# CSKB.net
KiCad netlist of a schematic drawn in EAGLE
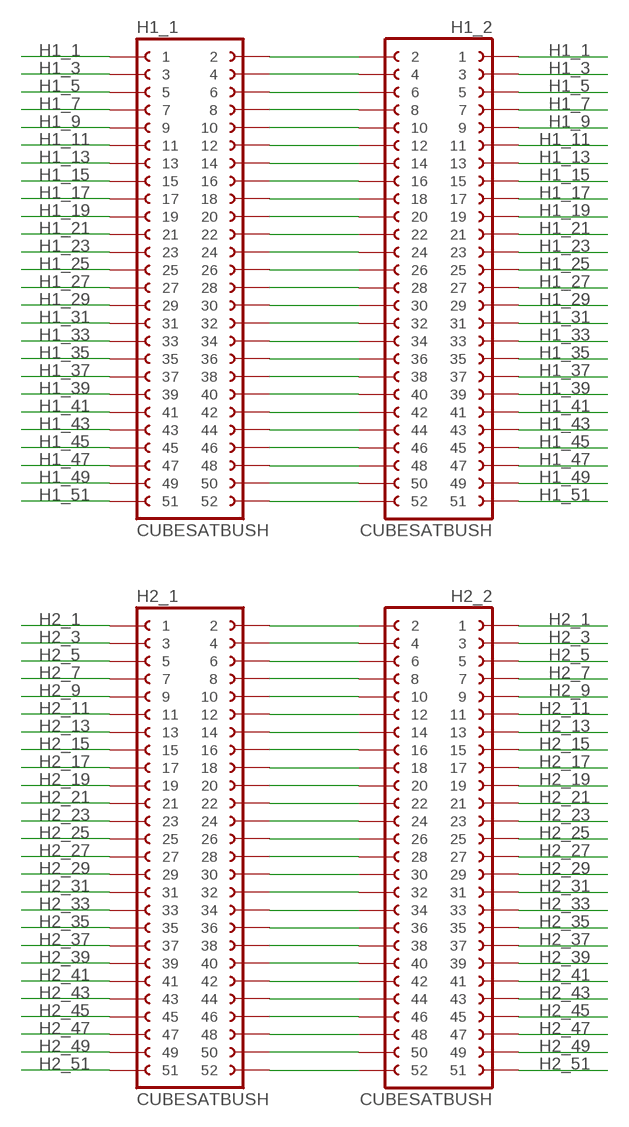
[diagram p0: schematic, sheet 1]

(export (version "E")
  (design (tool "Eeschema 10.0.6"))
  (components
    (comp (ref "H1_1")
      (value "CUBESATBUSH")
      (footprint "eagle-import:2X26HEADER")
      (fields (field (name "MPN") "TSW-126-07-G-D"))
      (libsource (lib "eagle-import") (part "CUBESATBUSH"))
    )
    (comp (ref "H1_2")
      (value "CUBESATBUSH")
      (footprint "eagle-import:2X26HEADER")
      (fields (field (name "MPN") "TSW-126-07-G-D"))
      (libsource (lib "eagle-import") (part "CUBESATBUSH"))
    )
    (comp (ref "H2_1")
      (value "CUBESATBUSH")
      (footprint "eagle-import:2X26HEADER")
      (fields (field (name "MPN") "TSW-126-07-G-D"))
      (libsource (lib "eagle-import") (part "CUBESATBUSH"))
    )
    (comp (ref "H2_2")
      (value "CUBESATBUSH")
      (footprint "eagle-import:2X26HEADER")
      (fields (field (name "MPN") "TSW-126-07-G-D"))
      (libsource (lib "eagle-import") (part "CUBESATBUSH"))
    )
  )
  (nets
    (net (code "1") (name "/H1_1") (class "Default")
      (node (ref "H1_1") (pin "1") (pinfunction "1_1") (pintype "passive"))
      (node (ref "H1_2") (pin "1") (pinfunction "1_1") (pintype "passive"))
    )
    (net (code "2") (name "/H1_3") (class "Default")
      (node (ref "H1_1") (pin "3") (pinfunction "3_3") (pintype "passive"))
      (node (ref "H1_2") (pin "3") (pinfunction "3_3") (pintype "passive"))
    )
    (net (code "3") (name "/H1_5") (class "Default")
      (node (ref "H1_1") (pin "5") (pinfunction "5_5") (pintype "passive"))
      (node (ref "H1_2") (pin "5") (pinfunction "5_5") (pintype "passive"))
    )
    (net (code "4") (name "/H1_7") (class "Default")
      (node (ref "H1_1") (pin "7") (pinfunction "7_7") (pintype "passive"))
      (node (ref "H1_2") (pin "7") (pinfunction "7_7") (pintype "passive"))
    )
    (net (code "5") (name "/H1_9") (class "Default")
      (node (ref "H1_1") (pin "9") (pinfunction "9_9") (pintype "passive"))
      (node (ref "H1_2") (pin "9") (pinfunction "9_9") (pintype "passive"))
    )
    (net (code "6") (name "/H1_11") (class "Default")
      (node (ref "H1_1") (pin "11") (pinfunction "11_11") (pintype "passive"))
      (node (ref "H1_2") (pin "11") (pinfunction "11_11") (pintype "passive"))
    )
    (net (code "7") (name "/H1_13") (class "Default")
      (node (ref "H1_1") (pin "13") (pinfunction "13_13") (pintype "passive"))
      (node (ref "H1_2") (pin "13") (pinfunction "13_13") (pintype "passive"))
    )
    (net (code "8") (name "/H1_15") (class "Default")
      (node (ref "H1_1") (pin "15") (pinfunction "15_15") (pintype "passive"))
      (node (ref "H1_2") (pin "15") (pinfunction "15_15") (pintype "passive"))
    )
    (net (code "9") (name "/H1_17") (class "Default")
      (node (ref "H1_1") (pin "17") (pinfunction "17_17") (pintype "passive"))
      (node (ref "H1_2") (pin "17") (pinfunction "17_17") (pintype "passive"))
    )
    (net (code "10") (name "/H1_19") (class "Default")
      (node (ref "H1_1") (pin "19") (pinfunction "19_19") (pintype "passive"))
      (node (ref "H1_2") (pin "19") (pinfunction "19_19") (pintype "passive"))
    )
    (net (code "11") (name "/H1_21") (class "Default")
      (node (ref "H1_1") (pin "21") (pinfunction "21_21") (pintype "passive"))
      (node (ref "H1_2") (pin "21") (pinfunction "21_21") (pintype "passive"))
    )
    (net (code "12") (name "/H1_23") (class "Default")
      (node (ref "H1_1") (pin "23") (pinfunction "23_23") (pintype "passive"))
      (node (ref "H1_2") (pin "23") (pinfunction "23_23") (pintype "passive"))
    )
    (net (code "13") (name "/H1_25") (class "Default")
      (node (ref "H1_1") (pin "25") (pinfunction "25_25") (pintype "passive"))
      (node (ref "H1_2") (pin "25") (pinfunction "25_25") (pintype "passive"))
    )
    (net (code "14") (name "/H1_27") (class "Default")
      (node (ref "H1_1") (pin "27") (pinfunction "27_27") (pintype "passive"))
      (node (ref "H1_2") (pin "27") (pinfunction "27_27") (pintype "passive"))
    )
    (net (code "15") (name "/H1_29") (class "Default")
      (node (ref "H1_1") (pin "29") (pinfunction "29_29") (pintype "passive"))
      (node (ref "H1_2") (pin "29") (pinfunction "29_29") (pintype "passive"))
    )
    (net (code "16") (name "/H1_31") (class "Default")
      (node (ref "H1_1") (pin "31") (pinfunction "31_31") (pintype "passive"))
      (node (ref "H1_2") (pin "31") (pinfunction "31_31") (pintype "passive"))
    )
    (net (code "17") (name "/H1_33") (class "Default")
      (node (ref "H1_1") (pin "33") (pinfunction "33_33") (pintype "passive"))
      (node (ref "H1_2") (pin "33") (pinfunction "33_33") (pintype "passive"))
    )
    (net (code "18") (name "/H1_35") (class "Default")
      (node (ref "H1_1") (pin "35") (pinfunction "35_35") (pintype "passive"))
      (node (ref "H1_2") (pin "35") (pinfunction "35_35") (pintype "passive"))
    )
    (net (code "19") (name "/H1_37") (class "Default")
      (node (ref "H1_1") (pin "37") (pinfunction "37_37") (pintype "passive"))
      (node (ref "H1_2") (pin "37") (pinfunction "37_37") (pintype "passive"))
    )
    (net (code "20") (name "/H1_39") (class "Default")
      (node (ref "H1_1") (pin "39") (pinfunction "39_39") (pintype "passive"))
      (node (ref "H1_2") (pin "39") (pinfunction "39_39") (pintype "passive"))
    )
    (net (code "21") (name "/H1_41") (class "Default")
      (node (ref "H1_1") (pin "41") (pinfunction "41_41") (pintype "passive"))
      (node (ref "H1_2") (pin "41") (pinfunction "41_41") (pintype "passive"))
    )
    (net (code "22") (name "/H1_43") (class "Default")
      (node (ref "H1_1") (pin "43") (pinfunction "43_43") (pintype "passive"))
      (node (ref "H1_2") (pin "43") (pinfunction "43_43") (pintype "passive"))
    )
    (net (code "23") (name "/H1_45") (class "Default")
      (node (ref "H1_1") (pin "45") (pinfunction "45_45") (pintype "passive"))
      (node (ref "H1_2") (pin "45") (pinfunction "45_45") (pintype "passive"))
    )
    (net (code "24") (name "/H1_47") (class "Default")
      (node (ref "H1_1") (pin "47") (pinfunction "47_47") (pintype "passive"))
      (node (ref "H1_2") (pin "47") (pinfunction "47_47") (pintype "passive"))
    )
    (net (code "25") (name "/H1_49") (class "Default")
      (node (ref "H1_1") (pin "49") (pinfunction "49_49") (pintype "passive"))
      (node (ref "H1_2") (pin "49") (pinfunction "49_49") (pintype "passive"))
    )
    (net (code "26") (name "/H1_51") (class "Default")
      (node (ref "H1_1") (pin "51") (pinfunction "51_51") (pintype "passive"))
      (node (ref "H1_2") (pin "51") (pinfunction "51_51") (pintype "passive"))
    )
    (net (code "27") (name "/H2_1") (class "Default")
      (node (ref "H2_1") (pin "1") (pinfunction "1_1") (pintype "passive"))
      (node (ref "H2_2") (pin "1") (pinfunction "1_1") (pintype "passive"))
    )
    (net (code "28") (name "/H2_3") (class "Default")
      (node (ref "H2_1") (pin "3") (pinfunction "3_3") (pintype "passive"))
      (node (ref "H2_2") (pin "3") (pinfunction "3_3") (pintype "passive"))
    )
    (net (code "29") (name "/H2_5") (class "Default")
      (node (ref "H2_1") (pin "5") (pinfunction "5_5") (pintype "passive"))
      (node (ref "H2_2") (pin "5") (pinfunction "5_5") (pintype "passive"))
    )
    (net (code "30") (name "/H2_7") (class "Default")
      (node (ref "H2_1") (pin "7") (pinfunction "7_7") (pintype "passive"))
      (node (ref "H2_2") (pin "7") (pinfunction "7_7") (pintype "passive"))
    )
    (net (code "31") (name "/H2_9") (class "Default")
      (node (ref "H2_1") (pin "9") (pinfunction "9_9") (pintype "passive"))
      (node (ref "H2_2") (pin "9") (pinfunction "9_9") (pintype "passive"))
    )
    (net (code "32") (name "/H2_11") (class "Default")
      (node (ref "H2_1") (pin "11") (pinfunction "11_11") (pintype "passive"))
      (node (ref "H2_2") (pin "11") (pinfunction "11_11") (pintype "passive"))
    )
    (net (code "33") (name "/H2_13") (class "Default")
      (node (ref "H2_1") (pin "13") (pinfunction "13_13") (pintype "passive"))
      (node (ref "H2_2") (pin "13") (pinfunction "13_13") (pintype "passive"))
    )
    (net (code "34") (name "/H2_15") (class "Default")
      (node (ref "H2_1") (pin "15") (pinfunction "15_15") (pintype "passive"))
      (node (ref "H2_2") (pin "15") (pinfunction "15_15") (pintype "passive"))
    )
    (net (code "35") (name "/H2_17") (class "Default")
      (node (ref "H2_1") (pin "17") (pinfunction "17_17") (pintype "passive"))
      (node (ref "H2_2") (pin "17") (pinfunction "17_17") (pintype "passive"))
    )
    (net (code "36") (name "/H2_19") (class "Default")
      (node (ref "H2_1") (pin "19") (pinfunction "19_19") (pintype "passive"))
      (node (ref "H2_2") (pin "19") (pinfunction "19_19") (pintype "passive"))
    )
    (net (code "37") (name "/H2_21") (class "Default")
      (node (ref "H2_1") (pin "21") (pinfunction "21_21") (pintype "passive"))
      (node (ref "H2_2") (pin "21") (pinfunction "21_21") (pintype "passive"))
    )
    (net (code "38") (name "/H2_23") (class "Default")
      (node (ref "H2_1") (pin "23") (pinfunction "23_23") (pintype "passive"))
      (node (ref "H2_2") (pin "23") (pinfunction "23_23") (pintype "passive"))
    )
    (net (code "39") (name "/H2_25") (class "Default")
      (node (ref "H2_1") (pin "25") (pinfunction "25_25") (pintype "passive"))
      (node (ref "H2_2") (pin "25") (pinfunction "25_25") (pintype "passive"))
    )
    (net (code "40") (name "/H2_27") (class "Default")
      (node (ref "H2_1") (pin "27") (pinfunction "27_27") (pintype "passive"))
      (node (ref "H2_2") (pin "27") (pinfunction "27_27") (pintype "passive"))
    )
    (net (code "41") (name "/H2_29") (class "Default")
      (node (ref "H2_1") (pin "29") (pinfunction "29_29") (pintype "passive"))
      (node (ref "H2_2") (pin "29") (pinfunction "29_29") (pintype "passive"))
    )
    (net (code "42") (name "/H2_31") (class "Default")
      (node (ref "H2_1") (pin "31") (pinfunction "31_31") (pintype "passive"))
      (node (ref "H2_2") (pin "31") (pinfunction "31_31") (pintype "passive"))
    )
    (net (code "43") (name "/H2_33") (class "Default")
      (node (ref "H2_1") (pin "33") (pinfunction "33_33") (pintype "passive"))
      (node (ref "H2_2") (pin "33") (pinfunction "33_33") (pintype "passive"))
    )
    (net (code "44") (name "/H2_35") (class "Default")
      (node (ref "H2_1") (pin "35") (pinfunction "35_35") (pintype "passive"))
      (node (ref "H2_2") (pin "35") (pinfunction "35_35") (pintype "passive"))
    )
    (net (code "45") (name "/H2_37") (class "Default")
      (node (ref "H2_1") (pin "37") (pinfunction "37_37") (pintype "passive"))
      (node (ref "H2_2") (pin "37") (pinfunction "37_37") (pintype "passive"))
    )
    (net (code "46") (name "/H2_39") (class "Default")
      (node (ref "H2_1") (pin "39") (pinfunction "39_39") (pintype "passive"))
      (node (ref "H2_2") (pin "39") (pinfunction "39_39") (pintype "passive"))
    )
    (net (code "47") (name "/H2_41") (class "Default")
      (node (ref "H2_1") (pin "41") (pinfunction "41_41") (pintype "passive"))
      (node (ref "H2_2") (pin "41") (pinfunction "41_41") (pintype "passive"))
    )
    (net (code "48") (name "/H2_43") (class "Default")
      (node (ref "H2_1") (pin "43") (pinfunction "43_43") (pintype "passive"))
      (node (ref "H2_2") (pin "43") (pinfunction "43_43") (pintype "passive"))
    )
    (net (code "49") (name "/H2_45") (class "Default")
      (node (ref "H2_1") (pin "45") (pinfunction "45_45") (pintype "passive"))
      (node (ref "H2_2") (pin "45") (pinfunction "45_45") (pintype "passive"))
    )
    (net (code "50") (name "/H2_47") (class "Default")
      (node (ref "H2_1") (pin "47") (pinfunction "47_47") (pintype "passive"))
      (node (ref "H2_2") (pin "47") (pinfunction "47_47") (pintype "passive"))
    )
    (net (code "51") (name "/H2_49") (class "Default")
      (node (ref "H2_1") (pin "49") (pinfunction "49_49") (pintype "passive"))
      (node (ref "H2_2") (pin "49") (pinfunction "49_49") (pintype "passive"))
    )
    (net (code "52") (name "/H2_51") (class "Default")
      (node (ref "H2_1") (pin "51") (pinfunction "51_51") (pintype "passive"))
      (node (ref "H2_2") (pin "51") (pinfunction "51_51") (pintype "passive"))
    )
    (net (code "53") (name "Net-(H1_1-Pad2)") (class "Default")
      (node (ref "H1_1") (pin "2") (pinfunction "2_2") (pintype "passive"))
      (node (ref "H1_2") (pin "2") (pinfunction "2_2") (pintype "passive"))
    )
    (net (code "54") (name "Net-(H1_1-Pad4)") (class "Default")
      (node (ref "H1_1") (pin "4") (pinfunction "4_4") (pintype "passive"))
      (node (ref "H1_2") (pin "4") (pinfunction "4_4") (pintype "passive"))
    )
    (net (code "55") (name "Net-(H1_1-Pad6)") (class "Default")
      (node (ref "H1_1") (pin "6") (pinfunction "6_6") (pintype "passive"))
      (node (ref "H1_2") (pin "6") (pinfunction "6_6") (pintype "passive"))
    )
    (net (code "56") (name "Net-(H1_1-Pad8)") (class "Default")
      (node (ref "H1_1") (pin "8") (pinfunction "8_8") (pintype "passive"))
      (node (ref "H1_2") (pin "8") (pinfunction "8_8") (pintype "passive"))
    )
    (net (code "57") (name "Net-(H1_1-Pad10)") (class "Default")
      (node (ref "H1_1") (pin "10") (pinfunction "10_10") (pintype "passive"))
      (node (ref "H1_2") (pin "10") (pinfunction "10_10") (pintype "passive"))
    )
    (net (code "58") (name "Net-(H1_1-Pad12)") (class "Default")
      (node (ref "H1_1") (pin "12") (pinfunction "12_12") (pintype "passive"))
      (node (ref "H1_2") (pin "12") (pinfunction "12_12") (pintype "passive"))
    )
    (net (code "59") (name "Net-(H1_1-Pad14)") (class "Default")
      (node (ref "H1_1") (pin "14") (pinfunction "14_14") (pintype "passive"))
      (node (ref "H1_2") (pin "14") (pinfunction "14_14") (pintype "passive"))
    )
    (net (code "60") (name "Net-(H1_1-Pad16)") (class "Default")
      (node (ref "H1_1") (pin "16") (pinfunction "16_16") (pintype "passive"))
      (node (ref "H1_2") (pin "16") (pinfunction "16_16") (pintype "passive"))
    )
    (net (code "61") (name "Net-(H1_1-Pad18)") (class "Default")
      (node (ref "H1_1") (pin "18") (pinfunction "18_18") (pintype "passive"))
      (node (ref "H1_2") (pin "18") (pinfunction "18_18") (pintype "passive"))
    )
    (net (code "62") (name "Net-(H1_1-Pad20)") (class "Default")
      (node (ref "H1_1") (pin "20") (pinfunction "20_20") (pintype "passive"))
      (node (ref "H1_2") (pin "20") (pinfunction "20_20") (pintype "passive"))
    )
    (net (code "63") (name "Net-(H1_1-Pad22)") (class "Default")
      (node (ref "H1_1") (pin "22") (pinfunction "22_22") (pintype "passive"))
      (node (ref "H1_2") (pin "22") (pinfunction "22_22") (pintype "passive"))
    )
    (net (code "64") (name "Net-(H1_1-Pad24)") (class "Default")
      (node (ref "H1_1") (pin "24") (pinfunction "24_24") (pintype "passive"))
      (node (ref "H1_2") (pin "24") (pinfunction "24_24") (pintype "passive"))
    )
    (net (code "65") (name "Net-(H1_1-Pad26)") (class "Default")
      (node (ref "H1_1") (pin "26") (pinfunction "26_26") (pintype "passive"))
      (node (ref "H1_2") (pin "26") (pinfunction "26_26") (pintype "passive"))
    )
    (net (code "66") (name "Net-(H1_1-Pad28)") (class "Default")
      (node (ref "H1_1") (pin "28") (pinfunction "28_28") (pintype "passive"))
      (node (ref "H1_2") (pin "28") (pinfunction "28_28") (pintype "passive"))
    )
    (net (code "67") (name "Net-(H1_1-Pad30)") (class "Default")
      (node (ref "H1_1") (pin "30") (pinfunction "30_30") (pintype "passive"))
      (node (ref "H1_2") (pin "30") (pinfunction "30_30") (pintype "passive"))
    )
    (net (code "68") (name "Net-(H1_1-Pad32)") (class "Default")
      (node (ref "H1_1") (pin "32") (pinfunction "32_32") (pintype "passive"))
      (node (ref "H1_2") (pin "32") (pinfunction "32_32") (pintype "passive"))
    )
    (net (code "69") (name "Net-(H1_1-Pad34)") (class "Default")
      (node (ref "H1_1") (pin "34") (pinfunction "34_34") (pintype "passive"))
      (node (ref "H1_2") (pin "34") (pinfunction "34_34") (pintype "passive"))
    )
    (net (code "70") (name "Net-(H1_1-Pad36)") (class "Default")
      (node (ref "H1_1") (pin "36") (pinfunction "36_36") (pintype "passive"))
      (node (ref "H1_2") (pin "36") (pinfunction "36_36") (pintype "passive"))
    )
    (net (code "71") (name "Net-(H1_1-Pad38)") (class "Default")
      (node (ref "H1_1") (pin "38") (pinfunction "38_38") (pintype "passive"))
      (node (ref "H1_2") (pin "38") (pinfunction "38_38") (pintype "passive"))
    )
    (net (code "72") (name "Net-(H1_1-Pad40)") (class "Default")
      (node (ref "H1_1") (pin "40") (pinfunction "40_40") (pintype "passive"))
      (node (ref "H1_2") (pin "40") (pinfunction "40_40") (pintype "passive"))
    )
    (net (code "73") (name "Net-(H1_1-Pad42)") (class "Default")
      (node (ref "H1_1") (pin "42") (pinfunction "42_42") (pintype "passive"))
      (node (ref "H1_2") (pin "42") (pinfunction "42_42") (pintype "passive"))
    )
    (net (code "74") (name "Net-(H1_1-Pad44)") (class "Default")
      (node (ref "H1_1") (pin "44") (pinfunction "44_44") (pintype "passive"))
      (node (ref "H1_2") (pin "44") (pinfunction "44_44") (pintype "passive"))
    )
    (net (code "75") (name "Net-(H1_1-Pad46)") (class "Default")
      (node (ref "H1_1") (pin "46") (pinfunction "46_46") (pintype "passive"))
      (node (ref "H1_2") (pin "46") (pinfunction "46_46") (pintype "passive"))
    )
    (net (code "76") (name "Net-(H1_1-Pad48)") (class "Default")
      (node (ref "H1_1") (pin "48") (pinfunction "48_48") (pintype "passive"))
      (node (ref "H1_2") (pin "48") (pinfunction "48_48") (pintype "passive"))
    )
    (net (code "77") (name "Net-(H1_1-Pad50)") (class "Default")
      (node (ref "H1_1") (pin "50") (pinfunction "50_50") (pintype "passive"))
      (node (ref "H1_2") (pin "50") (pinfunction "50_50") (pintype "passive"))
    )
    (net (code "78") (name "Net-(H1_1-Pad52)") (class "Default")
      (node (ref "H1_1") (pin "52") (pinfunction "52_52") (pintype "passive"))
      (node (ref "H1_2") (pin "52") (pinfunction "52_52") (pintype "passive"))
    )
    (net (code "79") (name "Net-(H2_1-Pad2)") (class "Default")
      (node (ref "H2_1") (pin "2") (pinfunction "2_2") (pintype "passive"))
      (node (ref "H2_2") (pin "2") (pinfunction "2_2") (pintype "passive"))
    )
    (net (code "80") (name "Net-(H2_1-Pad4)") (class "Default")
      (node (ref "H2_1") (pin "4") (pinfunction "4_4") (pintype "passive"))
      (node (ref "H2_2") (pin "4") (pinfunction "4_4") (pintype "passive"))
    )
    (net (code "81") (name "Net-(H2_1-Pad6)") (class "Default")
      (node (ref "H2_1") (pin "6") (pinfunction "6_6") (pintype "passive"))
      (node (ref "H2_2") (pin "6") (pinfunction "6_6") (pintype "passive"))
    )
    (net (code "82") (name "Net-(H2_1-Pad8)") (class "Default")
      (node (ref "H2_1") (pin "8") (pinfunction "8_8") (pintype "passive"))
      (node (ref "H2_2") (pin "8") (pinfunction "8_8") (pintype "passive"))
    )
    (net (code "83") (name "Net-(H2_1-Pad10)") (class "Default")
      (node (ref "H2_1") (pin "10") (pinfunction "10_10") (pintype "passive"))
      (node (ref "H2_2") (pin "10") (pinfunction "10_10") (pintype "passive"))
    )
    (net (code "84") (name "Net-(H2_1-Pad12)") (class "Default")
      (node (ref "H2_1") (pin "12") (pinfunction "12_12") (pintype "passive"))
      (node (ref "H2_2") (pin "12") (pinfunction "12_12") (pintype "passive"))
    )
    (net (code "85") (name "Net-(H2_1-Pad14)") (class "Default")
      (node (ref "H2_1") (pin "14") (pinfunction "14_14") (pintype "passive"))
      (node (ref "H2_2") (pin "14") (pinfunction "14_14") (pintype "passive"))
    )
    (net (code "86") (name "Net-(H2_1-Pad16)") (class "Default")
      (node (ref "H2_1") (pin "16") (pinfunction "16_16") (pintype "passive"))
      (node (ref "H2_2") (pin "16") (pinfunction "16_16") (pintype "passive"))
    )
    (net (code "87") (name "Net-(H2_1-Pad18)") (class "Default")
      (node (ref "H2_1") (pin "18") (pinfunction "18_18") (pintype "passive"))
      (node (ref "H2_2") (pin "18") (pinfunction "18_18") (pintype "passive"))
    )
    (net (code "88") (name "Net-(H2_1-Pad20)") (class "Default")
      (node (ref "H2_1") (pin "20") (pinfunction "20_20") (pintype "passive"))
      (node (ref "H2_2") (pin "20") (pinfunction "20_20") (pintype "passive"))
    )
    (net (code "89") (name "Net-(H2_1-Pad22)") (class "Default")
      (node (ref "H2_1") (pin "22") (pinfunction "22_22") (pintype "passive"))
      (node (ref "H2_2") (pin "22") (pinfunction "22_22") (pintype "passive"))
    )
    (net (code "90") (name "Net-(H2_1-Pad24)") (class "Default")
      (node (ref "H2_1") (pin "24") (pinfunction "24_24") (pintype "passive"))
      (node (ref "H2_2") (pin "24") (pinfunction "24_24") (pintype "passive"))
    )
    (net (code "91") (name "Net-(H2_1-Pad26)") (class "Default")
      (node (ref "H2_1") (pin "26") (pinfunction "26_26") (pintype "passive"))
      (node (ref "H2_2") (pin "26") (pinfunction "26_26") (pintype "passive"))
    )
    (net (code "92") (name "Net-(H2_1-Pad28)") (class "Default")
      (node (ref "H2_1") (pin "28") (pinfunction "28_28") (pintype "passive"))
      (node (ref "H2_2") (pin "28") (pinfunction "28_28") (pintype "passive"))
    )
    (net (code "93") (name "Net-(H2_1-Pad30)") (class "Default")
      (node (ref "H2_1") (pin "30") (pinfunction "30_30") (pintype "passive"))
      (node (ref "H2_2") (pin "30") (pinfunction "30_30") (pintype "passive"))
    )
    (net (code "94") (name "Net-(H2_1-Pad32)") (class "Default")
      (node (ref "H2_1") (pin "32") (pinfunction "32_32") (pintype "passive"))
      (node (ref "H2_2") (pin "32") (pinfunction "32_32") (pintype "passive"))
    )
    (net (code "95") (name "Net-(H2_1-Pad34)") (class "Default")
      (node (ref "H2_1") (pin "34") (pinfunction "34_34") (pintype "passive"))
      (node (ref "H2_2") (pin "34") (pinfunction "34_34") (pintype "passive"))
    )
    (net (code "96") (name "Net-(H2_1-Pad36)") (class "Default")
      (node (ref "H2_1") (pin "36") (pinfunction "36_36") (pintype "passive"))
      (node (ref "H2_2") (pin "36") (pinfunction "36_36") (pintype "passive"))
    )
    (net (code "97") (name "Net-(H2_1-Pad38)") (class "Default")
      (node (ref "H2_1") (pin "38") (pinfunction "38_38") (pintype "passive"))
      (node (ref "H2_2") (pin "38") (pinfunction "38_38") (pintype "passive"))
    )
    (net (code "98") (name "Net-(H2_1-Pad40)") (class "Default")
      (node (ref "H2_1") (pin "40") (pinfunction "40_40") (pintype "passive"))
      (node (ref "H2_2") (pin "40") (pinfunction "40_40") (pintype "passive"))
    )
    (net (code "99") (name "Net-(H2_1-Pad42)") (class "Default")
      (node (ref "H2_1") (pin "42") (pinfunction "42_42") (pintype "passive"))
      (node (ref "H2_2") (pin "42") (pinfunction "42_42") (pintype "passive"))
    )
    (net (code "100") (name "Net-(H2_1-Pad44)") (class "Default")
      (node (ref "H2_1") (pin "44") (pinfunction "44_44") (pintype "passive"))
      (node (ref "H2_2") (pin "44") (pinfunction "44_44") (pintype "passive"))
    )
    (net (code "101") (name "Net-(H2_1-Pad46)") (class "Default")
      (node (ref "H2_1") (pin "46") (pinfunction "46_46") (pintype "passive"))
      (node (ref "H2_2") (pin "46") (pinfunction "46_46") (pintype "passive"))
    )
    (net (code "102") (name "Net-(H2_1-Pad48)") (class "Default")
      (node (ref "H2_1") (pin "48") (pinfunction "48_48") (pintype "passive"))
      (node (ref "H2_2") (pin "48") (pinfunction "48_48") (pintype "passive"))
    )
    (net (code "103") (name "Net-(H2_1-Pad50)") (class "Default")
      (node (ref "H2_1") (pin "50") (pinfunction "50_50") (pintype "passive"))
      (node (ref "H2_2") (pin "50") (pinfunction "50_50") (pintype "passive"))
    )
    (net (code "104") (name "Net-(H2_1-Pad52)") (class "Default")
      (node (ref "H2_1") (pin "52") (pinfunction "52_52") (pintype "passive"))
      (node (ref "H2_2") (pin "52") (pinfunction "52_52") (pintype "passive"))
    )
  )
)
